# ENET.net
KiCad netlist of a schematic drawn in Altium Designer
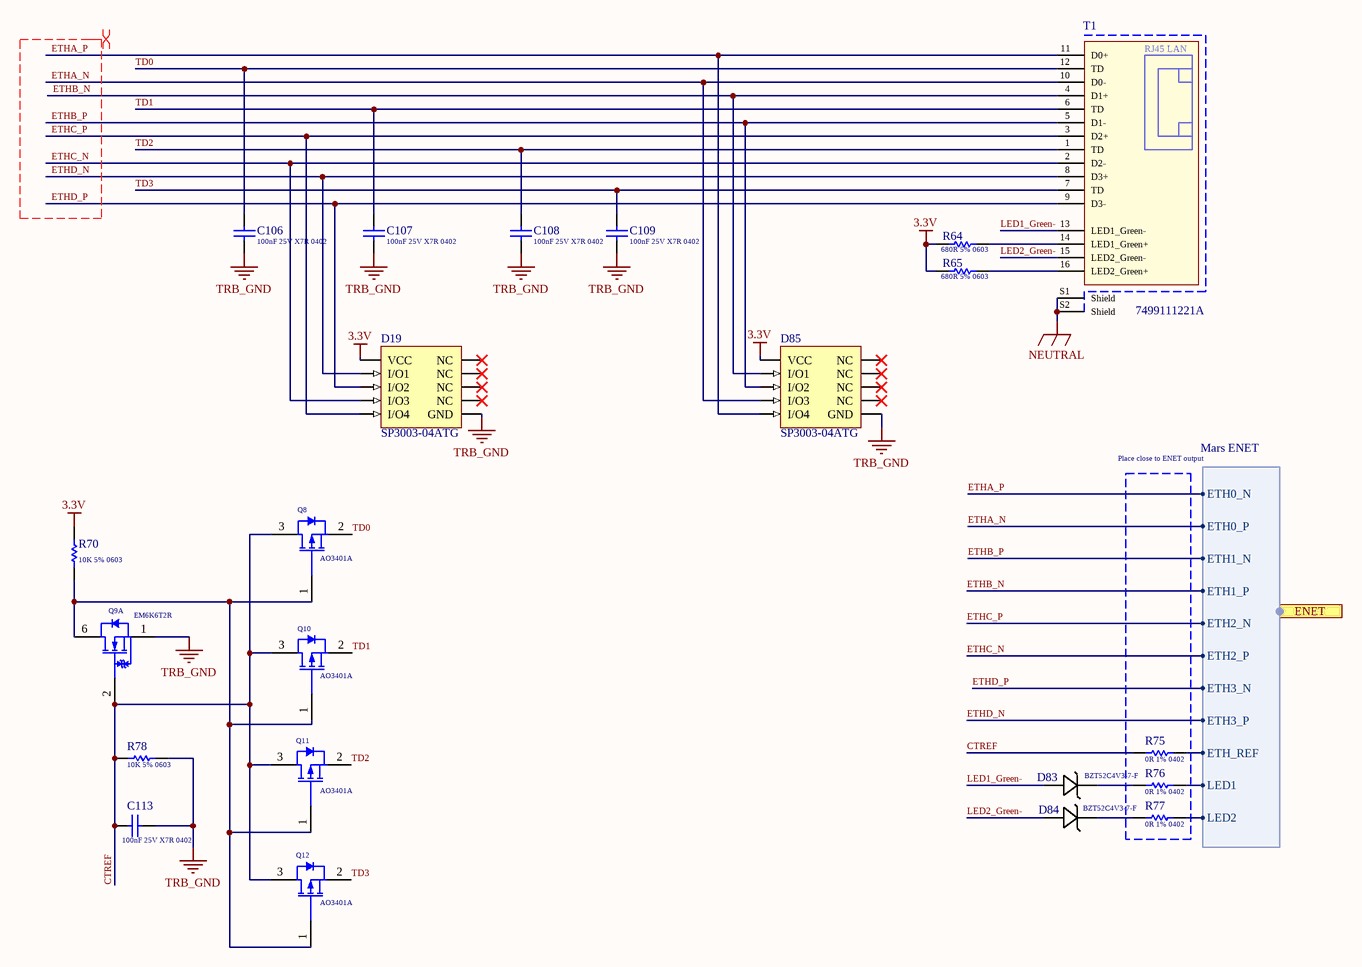
[diagram p0: ENET.SchDoc]

(export (version "E")
  (design (tool "Eeschema 10.0.6"))
  (components
    (comp (ref "C106")
      (value "Cap_Taiyo_Yuden_TMK105B7104KV-FR_100nF")
      (footprint "Cap_Taiyo_Yuden_TMK105B7104KV-FR_100nF")
      (description "CAP CER 100nF 25V X7R 0402")
      (fields (field (name "CAPACITANCE") "100nF 25V X7R 0402"))
      (libsource (lib "Cap_Taiyo_Yuden_TMK105B7104KV-FR_100nF") (part "Cap_Taiyo_Yuden_TMK105B7104KV-FR_100nF"))
    )
    (comp (ref "C107")
      (value "Cap_Taiyo_Yuden_TMK105B7104KV-FR_100nF")
      (footprint "Cap_Taiyo_Yuden_TMK105B7104KV-FR_100nF")
      (description "CAP CER 100nF 25V X7R 0402")
      (fields (field (name "CAPACITANCE") "100nF 25V X7R 0402"))
      (libsource (lib "Cap_Taiyo_Yuden_TMK105B7104KV-FR_100nF") (part "Cap_Taiyo_Yuden_TMK105B7104KV-FR_100nF"))
    )
    (comp (ref "C108")
      (value "Cap_Taiyo_Yuden_TMK105B7104KV-FR_100nF")
      (footprint "Cap_Taiyo_Yuden_TMK105B7104KV-FR_100nF")
      (description "CAP CER 100nF 25V X7R 0402")
      (fields (field (name "CAPACITANCE") "100nF 25V X7R 0402"))
      (libsource (lib "Cap_Taiyo_Yuden_TMK105B7104KV-FR_100nF") (part "Cap_Taiyo_Yuden_TMK105B7104KV-FR_100nF"))
    )
    (comp (ref "C109")
      (value "Cap_Taiyo_Yuden_TMK105B7104KV-FR_100nF")
      (footprint "Cap_Taiyo_Yuden_TMK105B7104KV-FR_100nF")
      (description "CAP CER 100nF 25V X7R 0402")
      (fields (field (name "CAPACITANCE") "100nF 25V X7R 0402"))
      (libsource (lib "Cap_Taiyo_Yuden_TMK105B7104KV-FR_100nF") (part "Cap_Taiyo_Yuden_TMK105B7104KV-FR_100nF"))
    )
    (comp (ref "C113")
      (value "Cap_Taiyo_Yuden_TMK105B7104KV-FR_100nF")
      (footprint "Cap_Taiyo_Yuden_TMK105B7104KV-FR_100nF")
      (description "CAP CER 100nF 25V X7R 0402")
      (fields (field (name "CAPACITANCE") "100nF 25V X7R 0402"))
      (libsource (lib "Cap_Taiyo_Yuden_TMK105B7104KV-FR_100nF") (part "Cap_Taiyo_Yuden_TMK105B7104KV-FR_100nF"))
    )
    (comp (ref "D19")
      (value "Diode_SP3003-04ATG_LVDS_ESD")
      (footprint "Diode_SP3003-04ATG_LVDS_ESD")
      (description "ESD Suppressors / TVS Diodes 4 Ch 8kV 0.65pF SPA")
      (fields (field (name "SERIES") "SP3003-04ATG"))
      (libsource (lib "Diode_SP3003-04ATG_LVDS_ESD") (part "Diode_SP3003-04ATG_LVDS_ESD"))
    )
    (comp (ref "D83")
      (value "BZT52C4V3-7-F")
      (footprint "SOD123")
      (description "Zener Diodes 500mW 4.3V Zener AEC-Q101 Qualified")
      (fields (field (name "SERIES") "BZT52C4V3-7-F"))
      (libsource (lib "4v3_zener_BZT52C4V3-7-F") (part "BZT52C4V3-7-F"))
    )
    (comp (ref "D84")
      (value "BZT52C4V3-7-F")
      (footprint "SOD123")
      (description "Zener Diodes 500mW 4.3V Zener AEC-Q101 Qualified")
      (fields (field (name "SERIES") "BZT52C4V3-7-F"))
      (libsource (lib "4v3_zener_BZT52C4V3-7-F") (part "BZT52C4V3-7-F"))
    )
    (comp (ref "D85")
      (value "Diode_SP3003-04ATG_LVDS_ESD")
      (footprint "Diode_SP3003-04ATG_LVDS_ESD")
      (description "ESD Suppressors / TVS Diodes 4 Ch 8kV 0.65pF SPA")
      (fields (field (name "SERIES") "SP3003-04ATG"))
      (libsource (lib "Diode_SP3003-04ATG_LVDS_ESD") (part "Diode_SP3003-04ATG_LVDS_ESD"))
    )
    (comp (ref "Q8")
      (value "Mos_Alpha&Omega_AO3401A_4A")
      (footprint "Mos_Alpha&Omega_AO3401A_4A")
      (description "P-Channel 30V 4A (Ta) 1.4W (Ta) Surface Mount SOT-23-3L")
      (fields (field (name "SERIES") "AO3401A"))
      (libsource (lib "Mos_Alpha&Omega_AO3401A_4A") (part "Mos_Alpha&Omega_AO3401A_4A"))
    )
    (comp (ref "Q9")
      (value "Mos_ROHM_EM6K6T2R_N_300mA")
      (footprint "Mos_ROHM_EM6K6T2R_N_300mA:Mos_ROHM_EM6K6T2R_N_300mA")
      (description "MOSFET Small Signal Dual N-CH 20V .3A .15W")
      (fields (field (name "SERIES") "EM6K6T2R"))
      (libsource (lib "Mos_ROHM_EM6K6T2R_N_300mA") (part "Mos_ROHM_EM6K6T2R_N_300mA"))
    )
    (comp (ref "Q10")
      (value "Mos_Alpha&Omega_AO3401A_4A")
      (footprint "Mos_Alpha&Omega_AO3401A_4A")
      (description "P-Channel 30V 4A (Ta) 1.4W (Ta) Surface Mount SOT-23-3L")
      (fields (field (name "SERIES") "AO3401A"))
      (libsource (lib "Mos_Alpha&Omega_AO3401A_4A") (part "Mos_Alpha&Omega_AO3401A_4A"))
    )
    (comp (ref "Q11")
      (value "Mos_Alpha&Omega_AO3401A_4A")
      (footprint "Mos_Alpha&Omega_AO3401A_4A")
      (description "P-Channel 30V 4A (Ta) 1.4W (Ta) Surface Mount SOT-23-3L")
      (fields (field (name "SERIES") "AO3401A"))
      (libsource (lib "Mos_Alpha&Omega_AO3401A_4A") (part "Mos_Alpha&Omega_AO3401A_4A"))
    )
    (comp (ref "Q12")
      (value "Mos_Alpha&Omega_AO3401A_4A")
      (footprint "Mos_Alpha&Omega_AO3401A_4A")
      (description "P-Channel 30V 4A (Ta) 1.4W (Ta) Surface Mount SOT-23-3L")
      (fields (field (name "SERIES") "AO3401A"))
      (libsource (lib "Mos_Alpha&Omega_AO3401A_4A") (part "Mos_Alpha&Omega_AO3401A_4A"))
    )
    (comp (ref "R64")
      (value "680R 5% 0603")
      (footprint "RESC0603(1608)_L")
      (description "680R 0.1W 5% 0603 (1608 Metric)  SMD")
      (fields (field (name "TOLERANCE") "5 %") (field (name "POWER") "0.1 W"))
      (libsource (lib "Altium Content Vault") (part "RES"))
    )
    (comp (ref "R65")
      (value "680R 5% 0603")
      (footprint "RESC0603(1608)_L")
      (description "680R 0.1W 5% 0603 (1608 Metric)  SMD")
      (fields (field (name "TOLERANCE") "5 %") (field (name "POWER") "0.1 W"))
      (libsource (lib "Altium Content Vault") (part "RES"))
    )
    (comp (ref "R70")
      (value "10K 5% 0603")
      (footprint "RESC0603(1608)_L")
      (description "10K 0.1W 5% 0603 (1608 Metric)  SMD")
      (fields (field (name "TOLERANCE") "5 %") (field (name "POWER") "0.1 W"))
      (libsource (lib "Altium Content Vault") (part "RES"))
    )
    (comp (ref "R75")
      (value "Res_Vishay_CRCW04020000Z0EDC_0_Ohm")
      (footprint "Res_Vishay_CRCW04020000Z0EDC_0_Ohm")
      (description "0R 0.062W 1% 0402 (1005 Metric)  SMD")
      (fields (field (name "RESISTANCE") "0R 1% 0402"))
      (libsource (lib "Res_Vishay_CRCW04020000Z0EDC_0_Ohm") (part "Res_Vishay_CRCW04020000Z0EDC_0_Ohm"))
    )
    (comp (ref "R76")
      (value "Res_Vishay_CRCW04020000Z0EDC_0_Ohm")
      (footprint "Res_Vishay_CRCW04020000Z0EDC_0_Ohm")
      (description "0R 0.062W 1% 0402 (1005 Metric)  SMD")
      (fields (field (name "RESISTANCE") "0R 1% 0402"))
      (libsource (lib "Res_Vishay_CRCW04020000Z0EDC_0_Ohm") (part "Res_Vishay_CRCW04020000Z0EDC_0_Ohm"))
    )
    (comp (ref "R77")
      (value "Res_Vishay_CRCW04020000Z0EDC_0_Ohm")
      (footprint "Res_Vishay_CRCW04020000Z0EDC_0_Ohm")
      (description "0R 0.062W 1% 0402 (1005 Metric)  SMD")
      (fields (field (name "RESISTANCE") "0R 1% 0402"))
      (libsource (lib "Res_Vishay_CRCW04020000Z0EDC_0_Ohm") (part "Res_Vishay_CRCW04020000Z0EDC_0_Ohm"))
    )
    (comp (ref "R78")
      (value "10K 5% 0603")
      (footprint "RESC0603(1608)_L")
      (description "10K 0.1W 5% 0603 (1608 Metric)  SMD")
      (fields (field (name "TOLERANCE") "5 %") (field (name "POWER") "0.1 W"))
      (libsource (lib "Altium Content Vault") (part "RES"))
    )
    (comp (ref "T1")
      (value "7499111221A")
      (footprint "7499111221A")
      (description "WE-RJ45 LAN Transformer, 10/100/1000 Base-T, THT, Port 1x1, Tab Up")
      (fields (field (name "PUBLISHER") "Wurth Elektronik"))
      (libsource (lib "Wurth-RJ45-7499111221A") (part "7499111221A"))
    )
  )
  (nets
    (net (code "3") (name "/CTREF") (class "Default")
      (node (ref "C113") (pin "2") (pinfunction "2_2") (pintype "passive"))
      (node (ref "Q10") (pin "3") (pinfunction "D_3") (pintype "passive"))
      (node (ref "Q11") (pin "3") (pinfunction "D_3") (pintype "passive"))
      (node (ref "Q12") (pin "3") (pinfunction "D_3") (pintype "passive"))
      (node (ref "Q8") (pin "3") (pinfunction "D_3") (pintype "passive"))
      (node (ref "Q9") (pin "2") (pinfunction "G_2") (pintype "passive"))
      (node (ref "R75") (pin "1") (pinfunction "1_1") (pintype "passive"))
      (node (ref "R78") (pin "2") (pinfunction "2_2") (pintype "passive"))
    )
    (net (code "4") (name "/ETHA_N") (class "Default")
      (node (ref "D85") (pin "4") (pinfunction "I/O3_4") (pintype "input"))
      (node (ref "T1") (pin "10") (pinfunction "D0-_10") (pintype "passive"))
    )
    (net (code "5") (name "/ETHA_P") (class "Default")
      (node (ref "D85") (pin "5") (pinfunction "I/O4_5") (pintype "input"))
      (node (ref "T1") (pin "11") (pinfunction "D0+_11") (pintype "passive"))
    )
    (net (code "6") (name "/ETHB_N") (class "Default")
      (node (ref "D85") (pin "1") (pinfunction "I/O1_1") (pintype "input"))
      (node (ref "T1") (pin "4") (pinfunction "D1+_4") (pintype "passive"))
    )
    (net (code "7") (name "/ETHB_P") (class "Default")
      (node (ref "D85") (pin "2") (pinfunction "I/O2_2") (pintype "input"))
      (node (ref "T1") (pin "5") (pinfunction "D1-_5") (pintype "passive"))
    )
    (net (code "8") (name "/ETHC_N") (class "Default")
      (node (ref "D19") (pin "4") (pinfunction "I/O3_4") (pintype "input"))
      (node (ref "T1") (pin "2") (pinfunction "D2-_2") (pintype "passive"))
    )
    (net (code "9") (name "/ETHC_P") (class "Default")
      (node (ref "D19") (pin "5") (pinfunction "I/O4_5") (pintype "input"))
      (node (ref "T1") (pin "3") (pinfunction "D2+_3") (pintype "passive"))
    )
    (net (code "10") (name "/ETHD_N") (class "Default")
      (node (ref "D19") (pin "1") (pinfunction "I/O1_1") (pintype "input"))
      (node (ref "T1") (pin "8") (pinfunction "D3+_8") (pintype "passive"))
    )
    (net (code "11") (name "/ETHD_P") (class "Default")
      (node (ref "D19") (pin "2") (pinfunction "I/O2_2") (pintype "input"))
      (node (ref "T1") (pin "9") (pinfunction "D3-_9") (pintype "passive"))
    )
    (net (code "12") (name "/ETH_REF") (class "Default")
      (node (ref "R75") (pin "2") (pinfunction "2_2") (pintype "passive"))
    )
    (net (code "13") (name "/LED1") (class "Default")
      (node (ref "R76") (pin "2") (pinfunction "2_2") (pintype "passive"))
    )
    (net (code "14") (name "/LED1_Green-") (class "Default")
      (node (ref "D83") (pin "2") (pinfunction "2_2") (pintype "passive"))
      (node (ref "T1") (pin "13") (pinfunction "LED1_Green-_13") (pintype "passive"))
    )
    (net (code "15") (name "/LED2") (class "Default")
      (node (ref "R77") (pin "2") (pinfunction "2_2") (pintype "passive"))
    )
    (net (code "16") (name "/LED2_Green-") (class "Default")
      (node (ref "D84") (pin "2") (pinfunction "2_2") (pintype "passive"))
      (node (ref "T1") (pin "15") (pinfunction "LED2_Green-_15") (pintype "passive"))
    )
    (net (code "17") (name "/TD0") (class "Default")
      (node (ref "C106") (pin "2") (pinfunction "2_2") (pintype "passive"))
      (node (ref "Q8") (pin "2") (pinfunction "S_2") (pintype "passive"))
      (node (ref "T1") (pin "12") (pinfunction "TD_12") (pintype "passive"))
    )
    (net (code "18") (name "/TD1") (class "Default")
      (node (ref "C107") (pin "2") (pinfunction "2_2") (pintype "passive"))
      (node (ref "Q10") (pin "2") (pinfunction "S_2") (pintype "passive"))
      (node (ref "T1") (pin "6") (pinfunction "TD_6") (pintype "passive"))
    )
    (net (code "19") (name "/TD2") (class "Default")
      (node (ref "C108") (pin "2") (pinfunction "2_2") (pintype "passive"))
      (node (ref "Q11") (pin "2") (pinfunction "S_2") (pintype "passive"))
      (node (ref "T1") (pin "1") (pinfunction "TD_1") (pintype "passive"))
    )
    (net (code "20") (name "/TD3") (class "Default")
      (node (ref "C109") (pin "2") (pinfunction "2_2") (pintype "passive"))
      (node (ref "Q12") (pin "2") (pinfunction "S_2") (pintype "passive"))
      (node (ref "T1") (pin "7") (pinfunction "TD_7") (pintype "passive"))
    )
    (net (code "22") (name "3.3V") (class "Default")
      (node (ref "D19") (pin "3") (pinfunction "VCC_3") (pintype "passive"))
      (node (ref "D85") (pin "3") (pinfunction "VCC_3") (pintype "passive"))
      (node (ref "R64") (pin "1") (pinfunction "1_1") (pintype "passive"))
      (node (ref "R65") (pin "1") (pinfunction "1_1") (pintype "passive"))
      (node (ref "R70") (pin "2") (pinfunction "2_2") (pintype "passive"))
    )
    (net (code "23") (name "NEUTRAL") (class "Default")
      (node (ref "T1") (pin "S1") (pinfunction "Shield_S1") (pintype "passive"))
      (node (ref "T1") (pin "S2") (pinfunction "Shield_S2") (pintype "passive"))
    )
    (net (code "24") (name "Net-(D83-Pad1)") (class "Default")
      (node (ref "D83") (pin "1") (pinfunction "1_1") (pintype "passive"))
      (node (ref "R76") (pin "1") (pinfunction "1_1") (pintype "passive"))
    )
    (net (code "25") (name "Net-(D84-Pad1)") (class "Default")
      (node (ref "D84") (pin "1") (pinfunction "1_1") (pintype "passive"))
      (node (ref "R77") (pin "1") (pinfunction "1_1") (pintype "passive"))
    )
    (net (code "26") (name "Net-(Q10-G)") (class "Default")
      (node (ref "Q10") (pin "1") (pinfunction "G_1") (pintype "passive"))
      (node (ref "Q11") (pin "1") (pinfunction "G_1") (pintype "passive"))
      (node (ref "Q12") (pin "1") (pinfunction "G_1") (pintype "passive"))
      (node (ref "Q8") (pin "1") (pinfunction "G_1") (pintype "passive"))
      (node (ref "Q9") (pin "6") (pinfunction "D_6") (pintype "passive"))
      (node (ref "R70") (pin "1") (pinfunction "1_1") (pintype "passive"))
    )
    (net (code "27") (name "Net-(T1-LED1_Green+)") (class "Default")
      (node (ref "R64") (pin "2") (pinfunction "2_2") (pintype "passive"))
      (node (ref "T1") (pin "14") (pinfunction "LED1_Green+_14") (pintype "passive"))
    )
    (net (code "28") (name "Net-(T1-LED2_Green+)") (class "Default")
      (node (ref "R65") (pin "2") (pinfunction "2_2") (pintype "passive"))
      (node (ref "T1") (pin "16") (pinfunction "LED2_Green+_16") (pintype "passive"))
    )
    (net (code "29") (name "TRB_GND") (class "Default")
      (node (ref "C106") (pin "1") (pinfunction "1_1") (pintype "passive"))
      (node (ref "C107") (pin "1") (pinfunction "1_1") (pintype "passive"))
      (node (ref "C108") (pin "1") (pinfunction "1_1") (pintype "passive"))
      (node (ref "C109") (pin "1") (pinfunction "1_1") (pintype "passive"))
      (node (ref "C113") (pin "1") (pinfunction "1_1") (pintype "passive"))
      (node (ref "D19") (pin "8") (pinfunction "GND_8") (pintype "power_in"))
      (node (ref "D85") (pin "8") (pinfunction "GND_8") (pintype "power_in"))
      (node (ref "Q9") (pin "1") (pinfunction "S_1") (pintype "passive"))
      (node (ref "R78") (pin "1") (pinfunction "1_1") (pintype "passive"))
    )
    (net (code "30") (name "unconnected-(D19-NC-Pad6)") (class "Default")
      (node (ref "D19") (pin "6") (pinfunction "NC_6") (pintype "tri_state+no_connect"))
    )
    (net (code "31") (name "unconnected-(D19-NC-Pad7)") (class "Default")
      (node (ref "D19") (pin "7") (pinfunction "NC_7") (pintype "tri_state+no_connect"))
    )
    (net (code "32") (name "unconnected-(D19-NC-Pad9)") (class "Default")
      (node (ref "D19") (pin "9") (pinfunction "NC_9") (pintype "tri_state+no_connect"))
    )
    (net (code "33") (name "unconnected-(D19-NC-Pad10)") (class "Default")
      (node (ref "D19") (pin "10") (pinfunction "NC_10") (pintype "tri_state+no_connect"))
    )
    (net (code "34") (name "unconnected-(D85-NC-Pad6)") (class "Default")
      (node (ref "D85") (pin "6") (pinfunction "NC_6") (pintype "tri_state+no_connect"))
    )
    (net (code "35") (name "unconnected-(D85-NC-Pad7)") (class "Default")
      (node (ref "D85") (pin "7") (pinfunction "NC_7") (pintype "tri_state+no_connect"))
    )
    (net (code "36") (name "unconnected-(D85-NC-Pad9)") (class "Default")
      (node (ref "D85") (pin "9") (pinfunction "NC_9") (pintype "tri_state+no_connect"))
    )
    (net (code "37") (name "unconnected-(D85-NC-Pad10)") (class "Default")
      (node (ref "D85") (pin "10") (pinfunction "NC_10") (pintype "tri_state+no_connect"))
    )
  )
)
